# minimumSystem_tugas_nanang.net
KiCad netlist of a schematic drawn in EAGLE
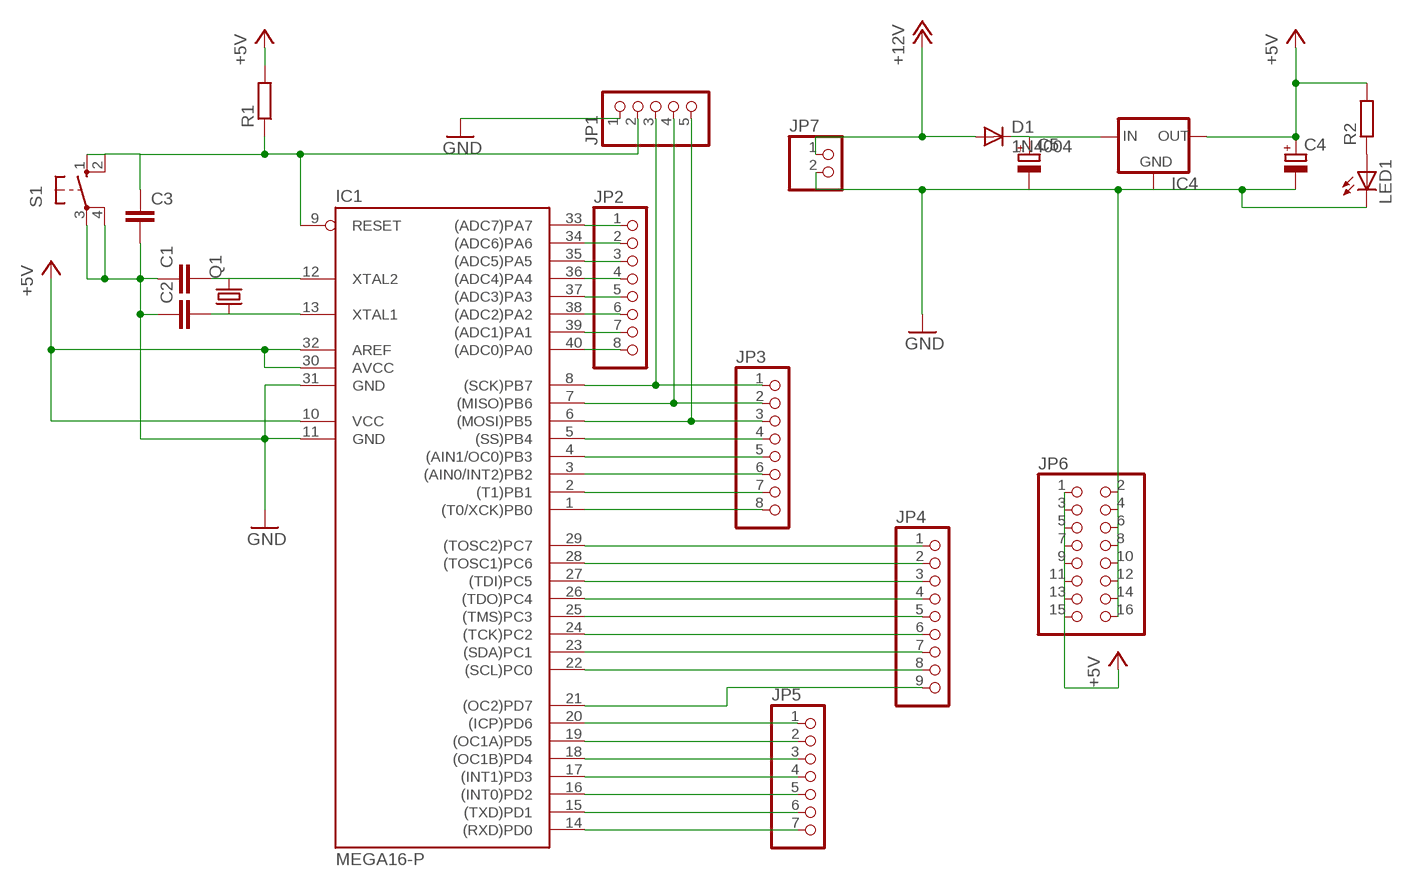
[diagram p0: schematic, sheet 1]

(export (version "E")
  (design (tool "Eeschema 10.0.6"))
  (components
    (comp (ref "C1")
      (value "C-EU025-024X044")
      (footprint "eagle-import:C025-024X044")
      (libsource (lib "eagle-import") (part "C-EU025-024X044"))
    )
    (comp (ref "C2")
      (value "C-EU025-024X044")
      (footprint "eagle-import:C025-024X044")
      (libsource (lib "eagle-import") (part "C-EU025-024X044"))
    )
    (comp (ref "C3")
      (value "C-EU050-025X075")
      (footprint "eagle-import:C050-025X075")
      (libsource (lib "eagle-import") (part "resistor_C-EU050-025X075"))
    )
    (comp (ref "C4")
      (value "CPOL-EUE2.5-5")
      (footprint "eagle-import:E2,5-5")
      (libsource (lib "eagle-import") (part "CPOL-EUE2.5-5"))
    )
    (comp (ref "C5")
      (value "CPOL-EUE2.5-5")
      (footprint "eagle-import:E2,5-5")
      (libsource (lib "eagle-import") (part "CPOL-EUE2.5-5"))
    )
    (comp (ref "D1")
      (value "1N4004")
      (footprint "eagle-import:DO41-10")
      (libsource (lib "eagle-import") (part "1N4004"))
    )
    (comp (ref "IC1")
      (value "MEGA16-P")
      (footprint "eagle-import:DIL40")
      (fields (field (name "MPN") "ATMEGA16-16PU"))
      (libsource (lib "eagle-import") (part "MEGA16-P"))
    )
    (comp (ref "IC4")
      (value "78XXS")
      (footprint "eagle-import:78XXS")
      (libsource (lib "eagle-import") (part "78XXS"))
    )
    (comp (ref "JP1")
      (value "PINHD-1X5")
      (footprint "eagle-import:1X05")
      (libsource (lib "eagle-import") (part "PINHD-1X5"))
    )
    (comp (ref "JP2")
      (value "PINHD-1X8")
      (footprint "eagle-import:1X08")
      (libsource (lib "eagle-import") (part "PINHD-1X8"))
    )
    (comp (ref "JP3")
      (value "PINHD-1X8")
      (footprint "eagle-import:1X08")
      (libsource (lib "eagle-import") (part "PINHD-1X8"))
    )
    (comp (ref "JP4")
      (value "PINHD-1X9")
      (footprint "eagle-import:1X09")
      (libsource (lib "eagle-import") (part "PINHD-1X9"))
    )
    (comp (ref "JP5")
      (value "PINHD-1X7")
      (footprint "eagle-import:1X07")
      (libsource (lib "eagle-import") (part "PINHD-1X7"))
    )
    (comp (ref "JP6")
      (value "PINHD-2X8")
      (footprint "eagle-import:2X08")
      (libsource (lib "eagle-import") (part "PINHD-2X8"))
    )
    (comp (ref "JP7")
      (value "PINHD-1X2")
      (footprint "eagle-import:1X02")
      (libsource (lib "eagle-import") (part "PINHD-1X2"))
    )
    (comp (ref "LED1")
      (value "LED5MM")
      (footprint "eagle-import:LED5MM")
      (libsource (lib "eagle-import") (part "LED5MM"))
    )
    (comp (ref "Q1")
      (value "CRYSTALHC49U-V")
      (footprint "eagle-import:HC49U-V")
      (libsource (lib "eagle-import") (part "CRYSTALHC49U-V"))
    )
    (comp (ref "R1")
      (value "R-EU_0204/7")
      (footprint "eagle-import:0204_7")
      (libsource (lib "eagle-import") (part "R-EU_0204/7"))
    )
    (comp (ref "R2")
      (value "R-EU_0204/7")
      (footprint "eagle-import:0204_7")
      (libsource (lib "eagle-import") (part "R-EU_0204/7"))
    )
    (comp (ref "S1")
      (value "10-XX")
      (footprint "eagle-import:B3F-10XX")
      (fields (field (name "MPN") "B3F-1000"))
      (libsource (lib "eagle-import") (part "10-XX"))
    )
  )
  (nets
    (net (code "1") (name "+5V") (class "Default")
      (node (ref "C4") (pin "+") (pinfunction "+_+") (pintype "passive"))
      (node (ref "IC1") (pin "10") (pinfunction "VCC_10") (pintype "power_in"))
      (node (ref "IC1") (pin "30") (pinfunction "AVCC_30") (pintype "power_in"))
      (node (ref "IC1") (pin "32") (pinfunction "AREF_32") (pintype "passive"))
      (node (ref "IC4") (pin "OUT") (pinfunction "OUT_OUT") (pintype "passive"))
      (node (ref "JP6") (pin "1") (pinfunction "1_1") (pintype "passive"))
      (node (ref "JP6") (pin "11") (pinfunction "11_11") (pintype "passive"))
      (node (ref "JP6") (pin "13") (pinfunction "13_13") (pintype "passive"))
      (node (ref "JP6") (pin "15") (pinfunction "15_15") (pintype "passive"))
      (node (ref "JP6") (pin "3") (pinfunction "3_3") (pintype "passive"))
      (node (ref "JP6") (pin "5") (pinfunction "5_5") (pintype "passive"))
      (node (ref "JP6") (pin "7") (pinfunction "7_7") (pintype "passive"))
      (node (ref "JP6") (pin "9") (pinfunction "9_9") (pintype "passive"))
      (node (ref "R1") (pin "2") (pinfunction "2_2") (pintype "passive"))
      (node (ref "R2") (pin "2") (pinfunction "2_2") (pintype "passive"))
    )
    (net (code "2") (name "+12V") (class "Default")
      (node (ref "D1") (pin "A") (pinfunction "A_A") (pintype "passive"))
      (node (ref "JP7") (pin "1") (pinfunction "1_1") (pintype "passive"))
    )
    (net (code "3") (name "GND") (class "Default")
      (node (ref "C1") (pin "1") (pinfunction "1_1") (pintype "passive"))
      (node (ref "C2") (pin "1") (pinfunction "1_1") (pintype "passive"))
      (node (ref "C3") (pin "2") (pinfunction "2_2") (pintype "passive"))
      (node (ref "C4") (pin "-") (pinfunction "-_-") (pintype "passive"))
      (node (ref "C5") (pin "-") (pinfunction "-_-") (pintype "passive"))
      (node (ref "IC1") (pin "11") (pinfunction "GND_11") (pintype "power_in"))
      (node (ref "IC1") (pin "31") (pinfunction "GND_31") (pintype "power_in"))
      (node (ref "IC4") (pin "GND") (pinfunction "GND_GND") (pintype "input"))
      (node (ref "JP1") (pin "1") (pinfunction "1_1") (pintype "passive"))
      (node (ref "JP6") (pin "10") (pinfunction "10_10") (pintype "passive"))
      (node (ref "JP6") (pin "12") (pinfunction "12_12") (pintype "passive"))
      (node (ref "JP6") (pin "14") (pinfunction "14_14") (pintype "passive"))
      (node (ref "JP6") (pin "16") (pinfunction "16_16") (pintype "passive"))
      (node (ref "JP6") (pin "2") (pinfunction "2_2") (pintype "passive"))
      (node (ref "JP6") (pin "4") (pinfunction "4_4") (pintype "passive"))
      (node (ref "JP6") (pin "6") (pinfunction "6_6") (pintype "passive"))
      (node (ref "JP6") (pin "8") (pinfunction "8_8") (pintype "passive"))
      (node (ref "JP7") (pin "2") (pinfunction "2_2") (pintype "passive"))
      (node (ref "LED1") (pin "K") (pinfunction "C_K") (pintype "passive"))
      (node (ref "S1") (pin "3") (pinfunction "P_3") (pintype "passive"))
      (node (ref "S1") (pin "4") (pinfunction "P1_4") (pintype "passive"))
    )
    (net (code "4") (name "Net-(C5-Pad+)") (class "Default")
      (node (ref "C5") (pin "+") (pinfunction "+_+") (pintype "passive"))
      (node (ref "D1") (pin "C") (pinfunction "C_C") (pintype "passive"))
      (node (ref "IC4") (pin "IN") (pinfunction "IN_IN") (pintype "input"))
    )
    (net (code "5") (name "Net-(IC1-(ADC0)PA0)") (class "Default")
      (node (ref "IC1") (pin "40") (pinfunction "(ADC0)PA0_40") (pintype "bidirectional"))
      (node (ref "JP2") (pin "8") (pinfunction "8_8") (pintype "passive"))
    )
    (net (code "6") (name "Net-(IC1-(ADC1)PA1)") (class "Default")
      (node (ref "IC1") (pin "39") (pinfunction "(ADC1)PA1_39") (pintype "bidirectional"))
      (node (ref "JP2") (pin "7") (pinfunction "7_7") (pintype "passive"))
    )
    (net (code "7") (name "Net-(IC1-(ADC2)PA2)") (class "Default")
      (node (ref "IC1") (pin "38") (pinfunction "(ADC2)PA2_38") (pintype "bidirectional"))
      (node (ref "JP2") (pin "6") (pinfunction "6_6") (pintype "passive"))
    )
    (net (code "8") (name "Net-(IC1-(ADC3)PA3)") (class "Default")
      (node (ref "IC1") (pin "37") (pinfunction "(ADC3)PA3_37") (pintype "bidirectional"))
      (node (ref "JP2") (pin "5") (pinfunction "5_5") (pintype "passive"))
    )
    (net (code "9") (name "Net-(IC1-(ADC4)PA4)") (class "Default")
      (node (ref "IC1") (pin "36") (pinfunction "(ADC4)PA4_36") (pintype "bidirectional"))
      (node (ref "JP2") (pin "4") (pinfunction "4_4") (pintype "passive"))
    )
    (net (code "10") (name "Net-(IC1-(ADC5)PA5)") (class "Default")
      (node (ref "IC1") (pin "35") (pinfunction "(ADC5)PA5_35") (pintype "bidirectional"))
      (node (ref "JP2") (pin "3") (pinfunction "3_3") (pintype "passive"))
    )
    (net (code "11") (name "Net-(IC1-(ADC6)PA6)") (class "Default")
      (node (ref "IC1") (pin "34") (pinfunction "(ADC6)PA6_34") (pintype "bidirectional"))
      (node (ref "JP2") (pin "2") (pinfunction "2_2") (pintype "passive"))
    )
    (net (code "12") (name "Net-(IC1-(ADC7)PA7)") (class "Default")
      (node (ref "IC1") (pin "33") (pinfunction "(ADC7)PA7_33") (pintype "bidirectional"))
      (node (ref "JP2") (pin "1") (pinfunction "1_1") (pintype "passive"))
    )
    (net (code "13") (name "Net-(IC1-(AIN0{slash}INT2)PB2)") (class "Default")
      (node (ref "IC1") (pin "3") (pinfunction "(AIN0/INT2)PB2_3") (pintype "bidirectional"))
      (node (ref "JP3") (pin "6") (pinfunction "6_6") (pintype "passive"))
    )
    (net (code "14") (name "Net-(IC1-(AIN1{slash}OC0)PB3)") (class "Default")
      (node (ref "IC1") (pin "4") (pinfunction "(AIN1/OC0)PB3_4") (pintype "bidirectional"))
      (node (ref "JP3") (pin "5") (pinfunction "5_5") (pintype "passive"))
    )
    (net (code "15") (name "Net-(IC1-(ICP)PD6)") (class "Default")
      (node (ref "IC1") (pin "20") (pinfunction "(ICP)PD6_20") (pintype "bidirectional"))
      (node (ref "JP5") (pin "1") (pinfunction "1_1") (pintype "passive"))
    )
    (net (code "16") (name "Net-(IC1-(INT0)PD2)") (class "Default")
      (node (ref "IC1") (pin "16") (pinfunction "(INT0)PD2_16") (pintype "bidirectional"))
      (node (ref "JP5") (pin "5") (pinfunction "5_5") (pintype "passive"))
    )
    (net (code "17") (name "Net-(IC1-(INT1)PD3)") (class "Default")
      (node (ref "IC1") (pin "17") (pinfunction "(INT1)PD3_17") (pintype "bidirectional"))
      (node (ref "JP5") (pin "4") (pinfunction "4_4") (pintype "passive"))
    )
    (net (code "18") (name "Net-(IC1-(MISO)PB6)") (class "Default")
      (node (ref "IC1") (pin "7") (pinfunction "(MISO)PB6_7") (pintype "bidirectional"))
      (node (ref "JP1") (pin "4") (pinfunction "4_4") (pintype "passive"))
      (node (ref "JP3") (pin "2") (pinfunction "2_2") (pintype "passive"))
    )
    (net (code "19") (name "Net-(IC1-(MOSI)PB5)") (class "Default")
      (node (ref "IC1") (pin "6") (pinfunction "(MOSI)PB5_6") (pintype "bidirectional"))
      (node (ref "JP1") (pin "5") (pinfunction "5_5") (pintype "passive"))
      (node (ref "JP3") (pin "3") (pinfunction "3_3") (pintype "passive"))
    )
    (net (code "20") (name "Net-(IC1-(OC1A)PD5)") (class "Default")
      (node (ref "IC1") (pin "19") (pinfunction "(OC1A)PD5_19") (pintype "bidirectional"))
      (node (ref "JP5") (pin "2") (pinfunction "2_2") (pintype "passive"))
    )
    (net (code "21") (name "Net-(IC1-(OC1B)PD4)") (class "Default")
      (node (ref "IC1") (pin "18") (pinfunction "(OC1B)PD4_18") (pintype "bidirectional"))
      (node (ref "JP5") (pin "3") (pinfunction "3_3") (pintype "passive"))
    )
    (net (code "22") (name "Net-(IC1-(OC2)PD7)") (class "Default")
      (node (ref "IC1") (pin "21") (pinfunction "(OC2)PD7_21") (pintype "bidirectional"))
      (node (ref "JP4") (pin "9") (pinfunction "9_9") (pintype "passive"))
    )
    (net (code "23") (name "Net-(IC1-(RXD)PD0)") (class "Default")
      (node (ref "IC1") (pin "14") (pinfunction "(RXD)PD0_14") (pintype "bidirectional"))
      (node (ref "JP5") (pin "7") (pinfunction "7_7") (pintype "passive"))
    )
    (net (code "24") (name "Net-(IC1-(SCK)PB7)") (class "Default")
      (node (ref "IC1") (pin "8") (pinfunction "(SCK)PB7_8") (pintype "bidirectional"))
      (node (ref "JP1") (pin "3") (pinfunction "3_3") (pintype "passive"))
      (node (ref "JP3") (pin "1") (pinfunction "1_1") (pintype "passive"))
    )
    (net (code "25") (name "Net-(IC1-(SCL)PC0)") (class "Default")
      (node (ref "IC1") (pin "22") (pinfunction "(SCL)PC0_22") (pintype "bidirectional"))
      (node (ref "JP4") (pin "8") (pinfunction "8_8") (pintype "passive"))
    )
    (net (code "26") (name "Net-(IC1-(SDA)PC1)") (class "Default")
      (node (ref "IC1") (pin "23") (pinfunction "(SDA)PC1_23") (pintype "bidirectional"))
      (node (ref "JP4") (pin "7") (pinfunction "7_7") (pintype "passive"))
    )
    (net (code "27") (name "Net-(IC1-(SS)PB4)") (class "Default")
      (node (ref "IC1") (pin "5") (pinfunction "(SS)PB4_5") (pintype "bidirectional"))
      (node (ref "JP3") (pin "4") (pinfunction "4_4") (pintype "passive"))
    )
    (net (code "28") (name "Net-(IC1-(T0{slash}XCK)PB0)") (class "Default")
      (node (ref "IC1") (pin "1") (pinfunction "(T0/XCK)PB0_1") (pintype "bidirectional"))
      (node (ref "JP3") (pin "8") (pinfunction "8_8") (pintype "passive"))
    )
    (net (code "29") (name "Net-(IC1-(T1)PB1)") (class "Default")
      (node (ref "IC1") (pin "2") (pinfunction "(T1)PB1_2") (pintype "bidirectional"))
      (node (ref "JP3") (pin "7") (pinfunction "7_7") (pintype "passive"))
    )
    (net (code "30") (name "Net-(IC1-(TCK)PC2)") (class "Default")
      (node (ref "IC1") (pin "24") (pinfunction "(TCK)PC2_24") (pintype "bidirectional"))
      (node (ref "JP4") (pin "6") (pinfunction "6_6") (pintype "passive"))
    )
    (net (code "31") (name "Net-(IC1-(TDI)PC5)") (class "Default")
      (node (ref "IC1") (pin "27") (pinfunction "(TDI)PC5_27") (pintype "bidirectional"))
      (node (ref "JP4") (pin "3") (pinfunction "3_3") (pintype "passive"))
    )
    (net (code "32") (name "Net-(IC1-(TDO)PC4)") (class "Default")
      (node (ref "IC1") (pin "26") (pinfunction "(TDO)PC4_26") (pintype "bidirectional"))
      (node (ref "JP4") (pin "4") (pinfunction "4_4") (pintype "passive"))
    )
    (net (code "33") (name "Net-(IC1-(TMS)PC3)") (class "Default")
      (node (ref "IC1") (pin "25") (pinfunction "(TMS)PC3_25") (pintype "bidirectional"))
      (node (ref "JP4") (pin "5") (pinfunction "5_5") (pintype "passive"))
    )
    (net (code "34") (name "Net-(IC1-(TOSC1)PC6)") (class "Default")
      (node (ref "IC1") (pin "28") (pinfunction "(TOSC1)PC6_28") (pintype "bidirectional"))
      (node (ref "JP4") (pin "2") (pinfunction "2_2") (pintype "passive"))
    )
    (net (code "35") (name "Net-(IC1-(TOSC2)PC7)") (class "Default")
      (node (ref "IC1") (pin "29") (pinfunction "(TOSC2)PC7_29") (pintype "bidirectional"))
      (node (ref "JP4") (pin "1") (pinfunction "1_1") (pintype "passive"))
    )
    (net (code "36") (name "Net-(IC1-(TXD)PD1)") (class "Default")
      (node (ref "IC1") (pin "15") (pinfunction "(TXD)PD1_15") (pintype "bidirectional"))
      (node (ref "JP5") (pin "6") (pinfunction "6_6") (pintype "passive"))
    )
    (net (code "37") (name "Net-(IC1-RESET)") (class "Default")
      (node (ref "C3") (pin "1") (pinfunction "1_1") (pintype "passive"))
      (node (ref "IC1") (pin "9") (pinfunction "RESET_9") (pintype "input"))
      (node (ref "JP1") (pin "2") (pinfunction "2_2") (pintype "passive"))
      (node (ref "R1") (pin "1") (pinfunction "1_1") (pintype "passive"))
      (node (ref "S1") (pin "1") (pinfunction "S_1") (pintype "passive"))
      (node (ref "S1") (pin "2") (pinfunction "S1_2") (pintype "passive"))
    )
    (net (code "38") (name "Net-(IC1-XTAL1)") (class "Default")
      (node (ref "C2") (pin "2") (pinfunction "2_2") (pintype "passive"))
      (node (ref "IC1") (pin "13") (pinfunction "XTAL1_13") (pintype "bidirectional"))
      (node (ref "Q1") (pin "1") (pinfunction "1_1") (pintype "passive"))
    )
    (net (code "39") (name "Net-(IC1-XTAL2)") (class "Default")
      (node (ref "C1") (pin "2") (pinfunction "2_2") (pintype "passive"))
      (node (ref "IC1") (pin "12") (pinfunction "XTAL2_12") (pintype "bidirectional"))
      (node (ref "Q1") (pin "2") (pinfunction "2_2") (pintype "passive"))
    )
    (net (code "40") (name "Net-(LED1-PadA)") (class "Default")
      (node (ref "LED1") (pin "A") (pinfunction "A_A") (pintype "passive"))
      (node (ref "R2") (pin "1") (pinfunction "1_1") (pintype "passive"))
    )
  )
)
